# trace_mockup-2-layer.net
KiCad netlist of a schematic drawn in EAGLE
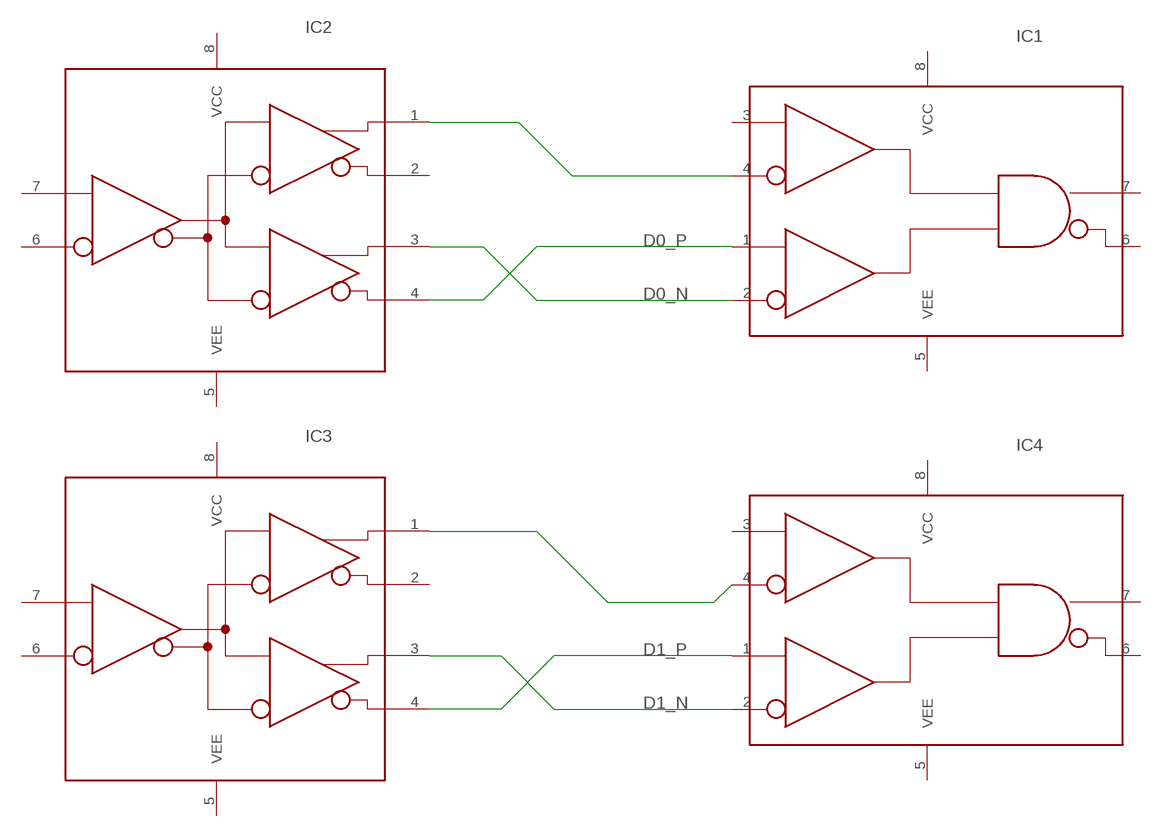
[diagram p0: schematic, sheet 1]

(export (version "E")
  (design (tool "Eeschema 10.0.6"))
  (components
    (comp (ref "IC1")
      (value "SY10EP05V")
      (footprint "eagle-import:SOIC8")
      (libsource (lib "eagle-import") (part "SY10EP05V"))
    )
    (comp (ref "IC2")
      (value "SY10EP11U")
      (footprint "eagle-import:SOIC8")
      (libsource (lib "eagle-import") (part "SY10EP11U"))
    )
    (comp (ref "IC3")
      (value "SY10EP11U")
      (footprint "eagle-import:SOIC8")
      (libsource (lib "eagle-import") (part "SY10EP11U"))
    )
    (comp (ref "IC4")
      (value "SY10EP05V")
      (footprint "eagle-import:SOIC8")
      (libsource (lib "eagle-import") (part "SY10EP05V"))
    )
  )
  (nets
    (net (code "1") (name "/D0_N") (class "Default")
      (node (ref "IC1") (pin "2") (pinfunction "~{D0}_2") (pintype "bidirectional"))
      (node (ref "IC2") (pin "3") (pinfunction "Q1_3") (pintype "bidirectional"))
    )
    (net (code "2") (name "/D0_P") (class "Default")
      (node (ref "IC1") (pin "1") (pinfunction "D0_1") (pintype "bidirectional"))
      (node (ref "IC2") (pin "4") (pinfunction "~{Q1}_4") (pintype "bidirectional"))
    )
    (net (code "3") (name "/D1_N") (class "Default")
      (node (ref "IC3") (pin "3") (pinfunction "Q1_3") (pintype "bidirectional"))
      (node (ref "IC4") (pin "2") (pinfunction "~{D0}_2") (pintype "bidirectional"))
    )
    (net (code "4") (name "/D1_P") (class "Default")
      (node (ref "IC3") (pin "4") (pinfunction "~{Q1}_4") (pintype "bidirectional"))
      (node (ref "IC4") (pin "1") (pinfunction "D0_1") (pintype "bidirectional"))
    )
    (net (code "5") (name "Net-(IC1-~{D1})") (class "Default")
      (node (ref "IC1") (pin "4") (pinfunction "~{D1}_4") (pintype "bidirectional"))
      (node (ref "IC2") (pin "1") (pinfunction "Q0_1") (pintype "bidirectional"))
    )
    (net (code "6") (name "Net-(IC3-Q0)") (class "Default")
      (node (ref "IC3") (pin "1") (pinfunction "Q0_1") (pintype "bidirectional"))
      (node (ref "IC4") (pin "4") (pinfunction "~{D1}_4") (pintype "bidirectional"))
    )
    (net (code "7") (name "unconnected-(IC1-D1-Pad3)") (class "Default")
      (node (ref "IC1") (pin "3") (pinfunction "D1_3") (pintype "bidirectional"))
    )
    (net (code "8") (name "unconnected-(IC1-Q-Pad7)") (class "Default")
      (node (ref "IC1") (pin "7") (pinfunction "Q_7") (pintype "bidirectional"))
    )
    (net (code "9") (name "unconnected-(IC1-VCC-Pad8)") (class "Default")
      (node (ref "IC1") (pin "8") (pinfunction "VCC_8") (pintype "bidirectional"))
    )
    (net (code "10") (name "unconnected-(IC1-VEE-Pad5)") (class "Default")
      (node (ref "IC1") (pin "5") (pinfunction "VEE_5") (pintype "bidirectional"))
    )
    (net (code "11") (name "unconnected-(IC1-~{Q}-Pad6)") (class "Default")
      (node (ref "IC1") (pin "6") (pinfunction "~{Q}_6") (pintype "bidirectional"))
    )
    (net (code "12") (name "unconnected-(IC2-D-Pad7)") (class "Default")
      (node (ref "IC2") (pin "7") (pinfunction "D_7") (pintype "bidirectional"))
    )
    (net (code "13") (name "unconnected-(IC2-VCC-Pad8)") (class "Default")
      (node (ref "IC2") (pin "8") (pinfunction "VCC_8") (pintype "bidirectional"))
    )
    (net (code "14") (name "unconnected-(IC2-VEE-Pad5)") (class "Default")
      (node (ref "IC2") (pin "5") (pinfunction "VEE_5") (pintype "bidirectional"))
    )
    (net (code "15") (name "unconnected-(IC2-~{D}-Pad6)") (class "Default")
      (node (ref "IC2") (pin "6") (pinfunction "~{D}_6") (pintype "bidirectional"))
    )
    (net (code "16") (name "unconnected-(IC2-~{Q0}-Pad2)") (class "Default")
      (node (ref "IC2") (pin "2") (pinfunction "~{Q0}_2") (pintype "bidirectional"))
    )
    (net (code "17") (name "unconnected-(IC3-D-Pad7)") (class "Default")
      (node (ref "IC3") (pin "7") (pinfunction "D_7") (pintype "bidirectional"))
    )
    (net (code "18") (name "unconnected-(IC3-VCC-Pad8)") (class "Default")
      (node (ref "IC3") (pin "8") (pinfunction "VCC_8") (pintype "bidirectional"))
    )
    (net (code "19") (name "unconnected-(IC3-VEE-Pad5)") (class "Default")
      (node (ref "IC3") (pin "5") (pinfunction "VEE_5") (pintype "bidirectional"))
    )
    (net (code "20") (name "unconnected-(IC3-~{D}-Pad6)") (class "Default")
      (node (ref "IC3") (pin "6") (pinfunction "~{D}_6") (pintype "bidirectional"))
    )
    (net (code "21") (name "unconnected-(IC3-~{Q0}-Pad2)") (class "Default")
      (node (ref "IC3") (pin "2") (pinfunction "~{Q0}_2") (pintype "bidirectional"))
    )
    (net (code "22") (name "unconnected-(IC4-D1-Pad3)") (class "Default")
      (node (ref "IC4") (pin "3") (pinfunction "D1_3") (pintype "bidirectional"))
    )
    (net (code "23") (name "unconnected-(IC4-Q-Pad7)") (class "Default")
      (node (ref "IC4") (pin "7") (pinfunction "Q_7") (pintype "bidirectional"))
    )
    (net (code "24") (name "unconnected-(IC4-VCC-Pad8)") (class "Default")
      (node (ref "IC4") (pin "8") (pinfunction "VCC_8") (pintype "bidirectional"))
    )
    (net (code "25") (name "unconnected-(IC4-VEE-Pad5)") (class "Default")
      (node (ref "IC4") (pin "5") (pinfunction "VEE_5") (pintype "bidirectional"))
    )
    (net (code "26") (name "unconnected-(IC4-~{Q}-Pad6)") (class "Default")
      (node (ref "IC4") (pin "6") (pinfunction "~{Q}_6") (pintype "bidirectional"))
    )
  )
)
